# Thermistors.net
KiCad netlist of a schematic drawn in Altium Designer
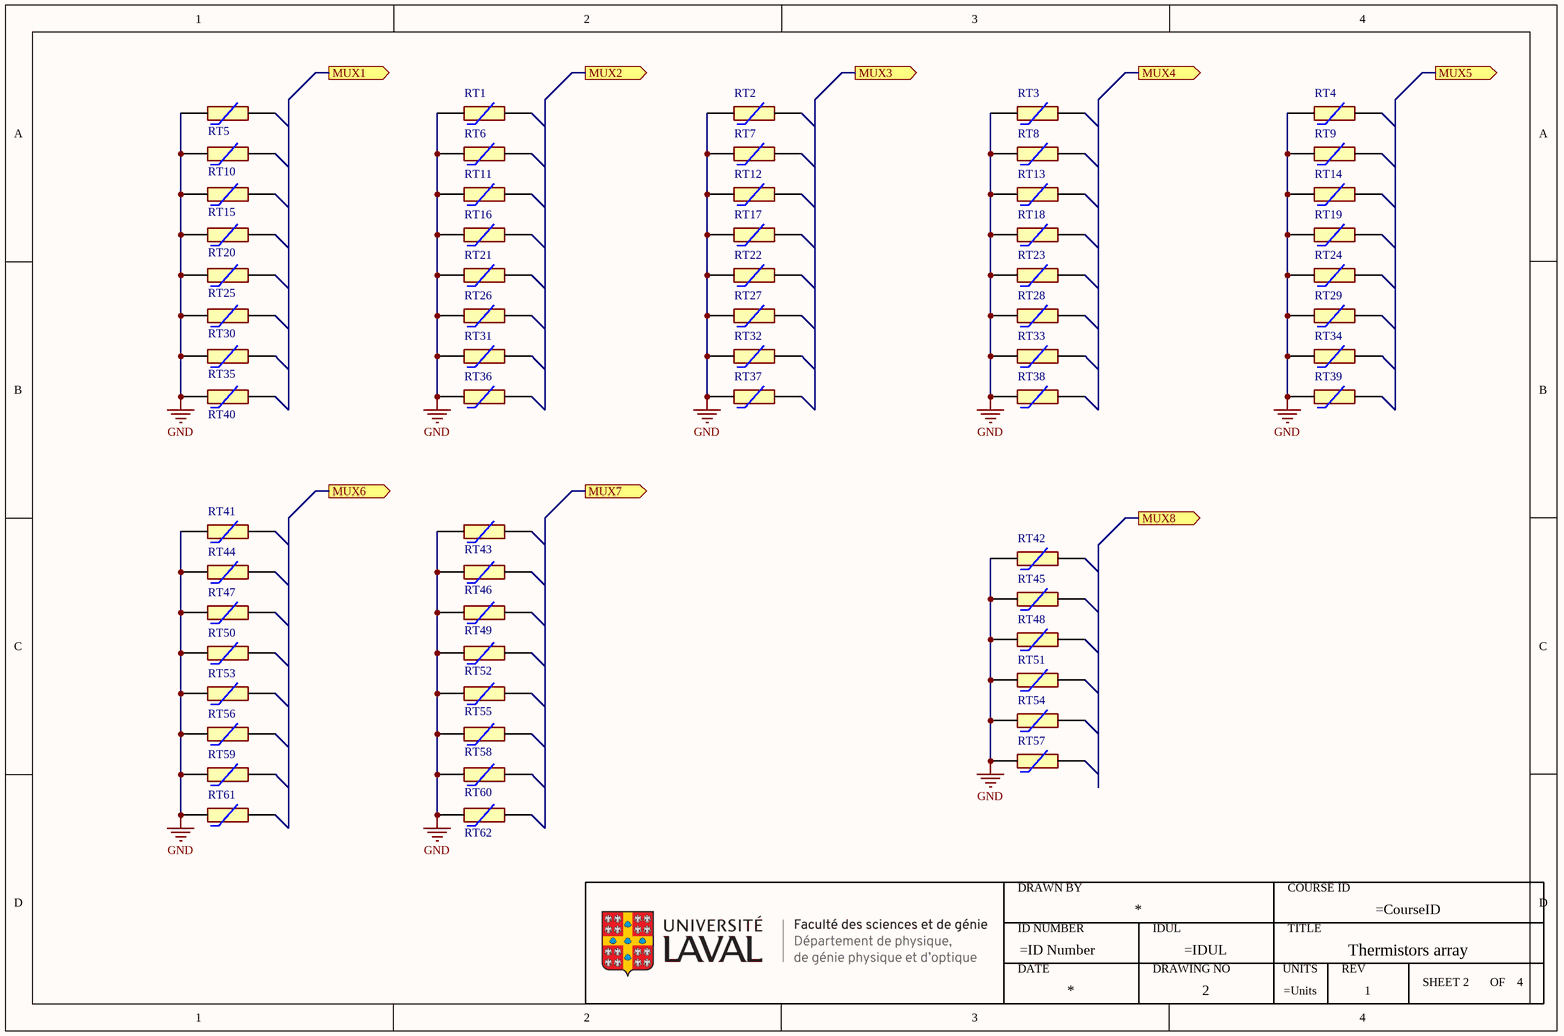
[diagram p0: Thermistors.SchDoc]

(export (version "E")
  (design (tool "Eeschema 10.0.6"))
  (components
    (comp (ref "*2")
      (value "ULaval FSG-DPGPO")
      (libsource (lib "ULaval Title Block") (part "ULaval FSG-DPGPO"))
    )
    (comp (ref "RT1")
      (value "NTCLE350E4103FHB0")
      (footprint "SamacSys:NTCLE350E4103FHB0")
      (description "Thermistor")
      (libsource (lib "*") (part "NTCLE350E4103FHB0"))
    )
    (comp (ref "RT2")
      (value "NTCLE350E4103FHB0")
      (footprint "SamacSys:NTCLE350E4103FHB0")
      (description "Thermistor")
      (libsource (lib "*") (part "NTCLE350E4103FHB0"))
    )
    (comp (ref "RT3")
      (value "NTCLE350E4103FHB0")
      (footprint "SamacSys:NTCLE350E4103FHB0")
      (description "Thermistor")
      (libsource (lib "*") (part "NTCLE350E4103FHB0"))
    )
    (comp (ref "RT4")
      (value "NTCLE350E4103FHB0")
      (footprint "SamacSys:NTCLE350E4103FHB0")
      (description "Thermistor")
      (libsource (lib "*") (part "NTCLE350E4103FHB0"))
    )
    (comp (ref "RT5")
      (value "NTCLE350E4103FHB0")
      (footprint "SamacSys:NTCLE350E4103FHB0")
      (description "Thermistor")
      (libsource (lib "*") (part "NTCLE350E4103FHB0"))
    )
    (comp (ref "RT6")
      (value "NTCLE350E4103FHB0")
      (footprint "SamacSys:NTCLE350E4103FHB0")
      (description "Thermistor")
      (libsource (lib "*") (part "NTCLE350E4103FHB0"))
    )
    (comp (ref "RT7")
      (value "NTCLE350E4103FHB0")
      (footprint "SamacSys:NTCLE350E4103FHB0")
      (description "Thermistor")
      (libsource (lib "*") (part "NTCLE350E4103FHB0"))
    )
    (comp (ref "RT8")
      (value "NTCLE350E4103FHB0")
      (footprint "SamacSys:NTCLE350E4103FHB0")
      (description "Thermistor")
      (libsource (lib "*") (part "NTCLE350E4103FHB0"))
    )
    (comp (ref "RT9")
      (value "NTCLE350E4103FHB0")
      (footprint "SamacSys:NTCLE350E4103FHB0")
      (description "Thermistor")
      (libsource (lib "*") (part "NTCLE350E4103FHB0"))
    )
    (comp (ref "RT10")
      (value "NTCLE350E4103FHB0")
      (footprint "SamacSys:NTCLE350E4103FHB0")
      (description "Thermistor")
      (libsource (lib "*") (part "NTCLE350E4103FHB0"))
    )
    (comp (ref "RT11")
      (value "NTCLE350E4103FHB0")
      (footprint "SamacSys:NTCLE350E4103FHB0")
      (description "Thermistor")
      (libsource (lib "*") (part "NTCLE350E4103FHB0"))
    )
    (comp (ref "RT12")
      (value "NTCLE350E4103FHB0")
      (footprint "SamacSys:NTCLE350E4103FHB0")
      (description "Thermistor")
      (libsource (lib "*") (part "NTCLE350E4103FHB0"))
    )
    (comp (ref "RT13")
      (value "NTCLE350E4103FHB0")
      (footprint "SamacSys:NTCLE350E4103FHB0")
      (description "Thermistor")
      (libsource (lib "*") (part "NTCLE350E4103FHB0"))
    )
    (comp (ref "RT14")
      (value "NTCLE350E4103FHB0")
      (footprint "SamacSys:NTCLE350E4103FHB0")
      (description "Thermistor")
      (libsource (lib "*") (part "NTCLE350E4103FHB0"))
    )
    (comp (ref "RT15")
      (value "NTCLE350E4103FHB0")
      (footprint "SamacSys:NTCLE350E4103FHB0")
      (description "Thermistor")
      (libsource (lib "*") (part "NTCLE350E4103FHB0"))
    )
    (comp (ref "RT16")
      (value "NTCLE350E4103FHB0")
      (footprint "SamacSys:NTCLE350E4103FHB0")
      (description "Thermistor")
      (libsource (lib "*") (part "NTCLE350E4103FHB0"))
    )
    (comp (ref "RT17")
      (value "NTCLE350E4103FHB0")
      (footprint "SamacSys:NTCLE350E4103FHB0")
      (description "Thermistor")
      (libsource (lib "*") (part "NTCLE350E4103FHB0"))
    )
    (comp (ref "RT18")
      (value "NTCLE350E4103FHB0")
      (footprint "SamacSys:NTCLE350E4103FHB0")
      (description "Thermistor")
      (libsource (lib "*") (part "NTCLE350E4103FHB0"))
    )
    (comp (ref "RT19")
      (value "NTCLE350E4103FHB0")
      (footprint "SamacSys:NTCLE350E4103FHB0")
      (description "Thermistor")
      (libsource (lib "*") (part "NTCLE350E4103FHB0"))
    )
    (comp (ref "RT20")
      (value "NTCLE350E4103FHB0")
      (footprint "SamacSys:NTCLE350E4103FHB0")
      (description "Thermistor")
      (libsource (lib "*") (part "NTCLE350E4103FHB0"))
    )
    (comp (ref "RT21")
      (value "NTCLE350E4103FHB0")
      (footprint "SamacSys:NTCLE350E4103FHB0")
      (description "Thermistor")
      (libsource (lib "*") (part "NTCLE350E4103FHB0"))
    )
    (comp (ref "RT22")
      (value "NTCLE350E4103FHB0")
      (footprint "SamacSys:NTCLE350E4103FHB0")
      (description "Thermistor")
      (libsource (lib "*") (part "NTCLE350E4103FHB0"))
    )
    (comp (ref "RT23")
      (value "NTCLE350E4103FHB0")
      (footprint "SamacSys:NTCLE350E4103FHB0")
      (description "Thermistor")
      (libsource (lib "*") (part "NTCLE350E4103FHB0"))
    )
    (comp (ref "RT24")
      (value "NTCLE350E4103FHB0")
      (footprint "SamacSys:NTCLE350E4103FHB0")
      (description "Thermistor")
      (libsource (lib "*") (part "NTCLE350E4103FHB0"))
    )
    (comp (ref "RT25")
      (value "NTCLE350E4103FHB0")
      (footprint "SamacSys:NTCLE350E4103FHB0")
      (description "Thermistor")
      (libsource (lib "*") (part "NTCLE350E4103FHB0"))
    )
    (comp (ref "RT26")
      (value "NTCLE350E4103FHB0")
      (footprint "SamacSys:NTCLE350E4103FHB0")
      (description "Thermistor")
      (libsource (lib "*") (part "NTCLE350E4103FHB0"))
    )
    (comp (ref "RT27")
      (value "NTCLE350E4103FHB0")
      (footprint "SamacSys:NTCLE350E4103FHB0")
      (description "Thermistor")
      (libsource (lib "*") (part "NTCLE350E4103FHB0"))
    )
    (comp (ref "RT28")
      (value "NTCLE350E4103FHB0")
      (footprint "SamacSys:NTCLE350E4103FHB0")
      (description "Thermistor")
      (libsource (lib "*") (part "NTCLE350E4103FHB0"))
    )
    (comp (ref "RT29")
      (value "NTCLE350E4103FHB0")
      (footprint "SamacSys:NTCLE350E4103FHB0")
      (description "Thermistor")
      (libsource (lib "*") (part "NTCLE350E4103FHB0"))
    )
    (comp (ref "RT30")
      (value "NTCLE350E4103FHB0")
      (footprint "SamacSys:NTCLE350E4103FHB0")
      (description "Thermistor")
      (libsource (lib "*") (part "NTCLE350E4103FHB0"))
    )
    (comp (ref "RT31")
      (value "NTCLE350E4103FHB0")
      (footprint "SamacSys:NTCLE350E4103FHB0")
      (description "Thermistor")
      (libsource (lib "*") (part "NTCLE350E4103FHB0"))
    )
    (comp (ref "RT32")
      (value "NTCLE350E4103FHB0")
      (footprint "SamacSys:NTCLE350E4103FHB0")
      (description "Thermistor")
      (libsource (lib "*") (part "NTCLE350E4103FHB0"))
    )
    (comp (ref "RT33")
      (value "NTCLE350E4103FHB0")
      (footprint "SamacSys:NTCLE350E4103FHB0")
      (description "Thermistor")
      (libsource (lib "*") (part "NTCLE350E4103FHB0"))
    )
    (comp (ref "RT34")
      (value "NTCLE350E4103FHB0")
      (footprint "SamacSys:NTCLE350E4103FHB0")
      (description "Thermistor")
      (libsource (lib "*") (part "NTCLE350E4103FHB0"))
    )
    (comp (ref "RT35")
      (value "NTCLE350E4103FHB0")
      (footprint "SamacSys:NTCLE350E4103FHB0")
      (description "Thermistor")
      (libsource (lib "*") (part "NTCLE350E4103FHB0"))
    )
    (comp (ref "RT36")
      (value "NTCLE350E4103FHB0")
      (footprint "SamacSys:NTCLE350E4103FHB0")
      (description "Thermistor")
      (libsource (lib "*") (part "NTCLE350E4103FHB0"))
    )
    (comp (ref "RT37")
      (value "NTCLE350E4103FHB0")
      (footprint "SamacSys:NTCLE350E4103FHB0")
      (description "Thermistor")
      (libsource (lib "*") (part "NTCLE350E4103FHB0"))
    )
    (comp (ref "RT38")
      (value "NTCLE350E4103FHB0")
      (footprint "SamacSys:NTCLE350E4103FHB0")
      (description "Thermistor")
      (libsource (lib "*") (part "NTCLE350E4103FHB0"))
    )
    (comp (ref "RT39")
      (value "NTCLE350E4103FHB0")
      (footprint "SamacSys:NTCLE350E4103FHB0")
      (description "Thermistor")
      (libsource (lib "*") (part "NTCLE350E4103FHB0"))
    )
    (comp (ref "RT40")
      (value "NTCLE350E4103FHB0")
      (footprint "SamacSys:NTCLE350E4103FHB0")
      (description "Thermistor")
      (libsource (lib "*") (part "NTCLE350E4103FHB0"))
    )
    (comp (ref "RT41")
      (value "NTCLE350E4103FHB0")
      (footprint "SamacSys:NTCLE350E4103FHB0")
      (description "Thermistor")
      (libsource (lib "*") (part "NTCLE350E4103FHB0"))
    )
    (comp (ref "RT42")
      (value "NTCLE350E4103FHB0")
      (footprint "SamacSys:NTCLE350E4103FHB0")
      (description "Thermistor")
      (libsource (lib "*") (part "NTCLE350E4103FHB0"))
    )
    (comp (ref "RT43")
      (value "NTCLE350E4103FHB0")
      (footprint "SamacSys:NTCLE350E4103FHB0")
      (description "Thermistor")
      (libsource (lib "*") (part "NTCLE350E4103FHB0"))
    )
    (comp (ref "RT44")
      (value "NTCLE350E4103FHB0")
      (footprint "SamacSys:NTCLE350E4103FHB0")
      (description "Thermistor")
      (libsource (lib "*") (part "NTCLE350E4103FHB0"))
    )
    (comp (ref "RT45")
      (value "NTCLE350E4103FHB0")
      (footprint "SamacSys:NTCLE350E4103FHB0")
      (description "Thermistor")
      (libsource (lib "*") (part "NTCLE350E4103FHB0"))
    )
    (comp (ref "RT46")
      (value "NTCLE350E4103FHB0")
      (footprint "SamacSys:NTCLE350E4103FHB0")
      (description "Thermistor")
      (libsource (lib "*") (part "NTCLE350E4103FHB0"))
    )
    (comp (ref "RT47")
      (value "NTCLE350E4103FHB0")
      (footprint "SamacSys:NTCLE350E4103FHB0")
      (description "Thermistor")
      (libsource (lib "*") (part "NTCLE350E4103FHB0"))
    )
    (comp (ref "RT48")
      (value "NTCLE350E4103FHB0")
      (footprint "SamacSys:NTCLE350E4103FHB0")
      (description "Thermistor")
      (libsource (lib "*") (part "NTCLE350E4103FHB0"))
    )
    (comp (ref "RT49")
      (value "NTCLE350E4103FHB0")
      (footprint "SamacSys:NTCLE350E4103FHB0")
      (description "Thermistor")
      (libsource (lib "*") (part "NTCLE350E4103FHB0"))
    )
    (comp (ref "RT50")
      (value "NTCLE350E4103FHB0")
      (footprint "SamacSys:NTCLE350E4103FHB0")
      (description "Thermistor")
      (libsource (lib "*") (part "NTCLE350E4103FHB0"))
    )
    (comp (ref "RT51")
      (value "NTCLE350E4103FHB0")
      (footprint "SamacSys:NTCLE350E4103FHB0")
      (description "Thermistor")
      (libsource (lib "*") (part "NTCLE350E4103FHB0"))
    )
    (comp (ref "RT52")
      (value "NTCLE350E4103FHB0")
      (footprint "SamacSys:NTCLE350E4103FHB0")
      (description "Thermistor")
      (libsource (lib "*") (part "NTCLE350E4103FHB0"))
    )
    (comp (ref "RT53")
      (value "NTCLE350E4103FHB0")
      (footprint "SamacSys:NTCLE350E4103FHB0")
      (description "Thermistor")
      (libsource (lib "*") (part "NTCLE350E4103FHB0"))
    )
    (comp (ref "RT54")
      (value "NTCLE350E4103FHB0")
      (footprint "SamacSys:NTCLE350E4103FHB0")
      (description "Thermistor")
      (libsource (lib "*") (part "NTCLE350E4103FHB0"))
    )
    (comp (ref "RT55")
      (value "NTCLE350E4103FHB0")
      (footprint "SamacSys:NTCLE350E4103FHB0")
      (description "Thermistor")
      (libsource (lib "*") (part "NTCLE350E4103FHB0"))
    )
    (comp (ref "RT56")
      (value "NTCLE350E4103FHB0")
      (footprint "SamacSys:NTCLE350E4103FHB0")
      (description "Thermistor")
      (libsource (lib "*") (part "NTCLE350E4103FHB0"))
    )
    (comp (ref "RT57")
      (value "NTCLE350E4103FHB0")
      (footprint "SamacSys:NTCLE350E4103FHB0")
      (description "Thermistor")
      (libsource (lib "*") (part "NTCLE350E4103FHB0"))
    )
    (comp (ref "RT58")
      (value "NTCLE350E4103FHB0")
      (footprint "SamacSys:NTCLE350E4103FHB0")
      (description "Thermistor")
      (libsource (lib "*") (part "NTCLE350E4103FHB0"))
    )
    (comp (ref "RT59")
      (value "NTCLE350E4103FHB0")
      (footprint "SamacSys:NTCLE350E4103FHB0")
      (description "Thermistor")
      (libsource (lib "*") (part "NTCLE350E4103FHB0"))
    )
    (comp (ref "RT60")
      (value "NTCLE350E4103FHB0")
      (footprint "SamacSys:NTCLE350E4103FHB0")
      (description "Thermistor")
      (libsource (lib "*") (part "NTCLE350E4103FHB0"))
    )
    (comp (ref "RT61")
      (value "NTCLE350E4103FHB0")
      (footprint "SamacSys:NTCLE350E4103FHB0")
      (description "Thermistor")
      (libsource (lib "*") (part "NTCLE350E4103FHB0"))
    )
    (comp (ref "RT62")
      (value "NTCLE350E4103FHB0")
      (footprint "SamacSys:NTCLE350E4103FHB0")
      (description "Thermistor")
      (libsource (lib "*") (part "NTCLE350E4103FHB0"))
    )
  )
  (nets
    (net (code "9") (name "GND") (class "Default")
      (node (ref "RT1") (pin "1") (pinfunction "1_1") (pintype "passive"))
      (node (ref "RT10") (pin "1") (pinfunction "1_1") (pintype "passive"))
      (node (ref "RT11") (pin "1") (pinfunction "1_1") (pintype "passive"))
      (node (ref "RT12") (pin "1") (pinfunction "1_1") (pintype "passive"))
      (node (ref "RT13") (pin "1") (pinfunction "1_1") (pintype "passive"))
      (node (ref "RT14") (pin "1") (pinfunction "1_1") (pintype "passive"))
      (node (ref "RT15") (pin "1") (pinfunction "1_1") (pintype "passive"))
      (node (ref "RT16") (pin "1") (pinfunction "1_1") (pintype "passive"))
      (node (ref "RT17") (pin "1") (pinfunction "1_1") (pintype "passive"))
      (node (ref "RT18") (pin "1") (pinfunction "1_1") (pintype "passive"))
      (node (ref "RT19") (pin "1") (pinfunction "1_1") (pintype "passive"))
      (node (ref "RT2") (pin "1") (pinfunction "1_1") (pintype "passive"))
      (node (ref "RT20") (pin "1") (pinfunction "1_1") (pintype "passive"))
      (node (ref "RT21") (pin "1") (pinfunction "1_1") (pintype "passive"))
      (node (ref "RT22") (pin "1") (pinfunction "1_1") (pintype "passive"))
      (node (ref "RT23") (pin "1") (pinfunction "1_1") (pintype "passive"))
      (node (ref "RT24") (pin "1") (pinfunction "1_1") (pintype "passive"))
      (node (ref "RT25") (pin "1") (pinfunction "1_1") (pintype "passive"))
      (node (ref "RT26") (pin "1") (pinfunction "1_1") (pintype "passive"))
      (node (ref "RT27") (pin "1") (pinfunction "1_1") (pintype "passive"))
      (node (ref "RT28") (pin "1") (pinfunction "1_1") (pintype "passive"))
      (node (ref "RT29") (pin "1") (pinfunction "1_1") (pintype "passive"))
      (node (ref "RT3") (pin "1") (pinfunction "1_1") (pintype "passive"))
      (node (ref "RT30") (pin "1") (pinfunction "1_1") (pintype "passive"))
      (node (ref "RT31") (pin "1") (pinfunction "1_1") (pintype "passive"))
      (node (ref "RT32") (pin "1") (pinfunction "1_1") (pintype "passive"))
      (node (ref "RT33") (pin "1") (pinfunction "1_1") (pintype "passive"))
      (node (ref "RT34") (pin "1") (pinfunction "1_1") (pintype "passive"))
      (node (ref "RT35") (pin "1") (pinfunction "1_1") (pintype "passive"))
      (node (ref "RT36") (pin "1") (pinfunction "1_1") (pintype "passive"))
      (node (ref "RT37") (pin "1") (pinfunction "1_1") (pintype "passive"))
      (node (ref "RT38") (pin "1") (pinfunction "1_1") (pintype "passive"))
      (node (ref "RT39") (pin "1") (pinfunction "1_1") (pintype "passive"))
      (node (ref "RT4") (pin "1") (pinfunction "1_1") (pintype "passive"))
      (node (ref "RT40") (pin "1") (pinfunction "1_1") (pintype "passive"))
      (node (ref "RT41") (pin "1") (pinfunction "1_1") (pintype "passive"))
      (node (ref "RT42") (pin "1") (pinfunction "1_1") (pintype "passive"))
      (node (ref "RT43") (pin "1") (pinfunction "1_1") (pintype "passive"))
      (node (ref "RT44") (pin "1") (pinfunction "1_1") (pintype "passive"))
      (node (ref "RT45") (pin "1") (pinfunction "1_1") (pintype "passive"))
      (node (ref "RT46") (pin "1") (pinfunction "1_1") (pintype "passive"))
      (node (ref "RT47") (pin "1") (pinfunction "1_1") (pintype "passive"))
      (node (ref "RT48") (pin "1") (pinfunction "1_1") (pintype "passive"))
      (node (ref "RT49") (pin "1") (pinfunction "1_1") (pintype "passive"))
      (node (ref "RT5") (pin "1") (pinfunction "1_1") (pintype "passive"))
      (node (ref "RT50") (pin "1") (pinfunction "1_1") (pintype "passive"))
      (node (ref "RT51") (pin "1") (pinfunction "1_1") (pintype "passive"))
      (node (ref "RT52") (pin "1") (pinfunction "1_1") (pintype "passive"))
      (node (ref "RT53") (pin "1") (pinfunction "1_1") (pintype "passive"))
      (node (ref "RT54") (pin "1") (pinfunction "1_1") (pintype "passive"))
      (node (ref "RT55") (pin "1") (pinfunction "1_1") (pintype "passive"))
      (node (ref "RT56") (pin "1") (pinfunction "1_1") (pintype "passive"))
      (node (ref "RT57") (pin "1") (pinfunction "1_1") (pintype "passive"))
      (node (ref "RT58") (pin "1") (pinfunction "1_1") (pintype "passive"))
      (node (ref "RT59") (pin "1") (pinfunction "1_1") (pintype "passive"))
      (node (ref "RT6") (pin "1") (pinfunction "1_1") (pintype "passive"))
      (node (ref "RT60") (pin "1") (pinfunction "1_1") (pintype "passive"))
      (node (ref "RT61") (pin "1") (pinfunction "1_1") (pintype "passive"))
      (node (ref "RT62") (pin "1") (pinfunction "1_1") (pintype "passive"))
      (node (ref "RT7") (pin "1") (pinfunction "1_1") (pintype "passive"))
      (node (ref "RT8") (pin "1") (pinfunction "1_1") (pintype "passive"))
      (node (ref "RT9") (pin "1") (pinfunction "1_1") (pintype "passive"))
    )
    (net (code "10") (name "unconnected-(RT1-Pad2)") (class "Default")
      (node (ref "RT1") (pin "2") (pinfunction "2_2") (pintype "passive"))
    )
    (net (code "11") (name "unconnected-(RT2-Pad2)") (class "Default")
      (node (ref "RT2") (pin "2") (pinfunction "2_2") (pintype "passive"))
    )
    (net (code "12") (name "unconnected-(RT3-Pad2)") (class "Default")
      (node (ref "RT3") (pin "2") (pinfunction "2_2") (pintype "passive"))
    )
    (net (code "13") (name "unconnected-(RT4-Pad2)") (class "Default")
      (node (ref "RT4") (pin "2") (pinfunction "2_2") (pintype "passive"))
    )
    (net (code "14") (name "unconnected-(RT5-Pad2)") (class "Default")
      (node (ref "RT5") (pin "2") (pinfunction "2_2") (pintype "passive"))
    )
    (net (code "15") (name "unconnected-(RT6-Pad2)") (class "Default")
      (node (ref "RT6") (pin "2") (pinfunction "2_2") (pintype "passive"))
    )
    (net (code "16") (name "unconnected-(RT7-Pad2)") (class "Default")
      (node (ref "RT7") (pin "2") (pinfunction "2_2") (pintype "passive"))
    )
    (net (code "17") (name "unconnected-(RT8-Pad2)") (class "Default")
      (node (ref "RT8") (pin "2") (pinfunction "2_2") (pintype "passive"))
    )
    (net (code "18") (name "unconnected-(RT9-Pad2)") (class "Default")
      (node (ref "RT9") (pin "2") (pinfunction "2_2") (pintype "passive"))
    )
    (net (code "19") (name "unconnected-(RT10-Pad2)") (class "Default")
      (node (ref "RT10") (pin "2") (pinfunction "2_2") (pintype "passive"))
    )
    (net (code "20") (name "unconnected-(RT11-Pad2)") (class "Default")
      (node (ref "RT11") (pin "2") (pinfunction "2_2") (pintype "passive"))
    )
    (net (code "21") (name "unconnected-(RT12-Pad2)") (class "Default")
      (node (ref "RT12") (pin "2") (pinfunction "2_2") (pintype "passive"))
    )
    (net (code "22") (name "unconnected-(RT13-Pad2)") (class "Default")
      (node (ref "RT13") (pin "2") (pinfunction "2_2") (pintype "passive"))
    )
    (net (code "23") (name "unconnected-(RT14-Pad2)") (class "Default")
      (node (ref "RT14") (pin "2") (pinfunction "2_2") (pintype "passive"))
    )
    (net (code "24") (name "unconnected-(RT15-Pad2)") (class "Default")
      (node (ref "RT15") (pin "2") (pinfunction "2_2") (pintype "passive"))
    )
    (net (code "25") (name "unconnected-(RT16-Pad2)") (class "Default")
      (node (ref "RT16") (pin "2") (pinfunction "2_2") (pintype "passive"))
    )
    (net (code "26") (name "unconnected-(RT17-Pad2)") (class "Default")
      (node (ref "RT17") (pin "2") (pinfunction "2_2") (pintype "passive"))
    )
    (net (code "27") (name "unconnected-(RT18-Pad2)") (class "Default")
      (node (ref "RT18") (pin "2") (pinfunction "2_2") (pintype "passive"))
    )
    (net (code "28") (name "unconnected-(RT19-Pad2)") (class "Default")
      (node (ref "RT19") (pin "2") (pinfunction "2_2") (pintype "passive"))
    )
    (net (code "29") (name "unconnected-(RT20-Pad2)") (class "Default")
      (node (ref "RT20") (pin "2") (pinfunction "2_2") (pintype "passive"))
    )
    (net (code "30") (name "unconnected-(RT21-Pad2)") (class "Default")
      (node (ref "RT21") (pin "2") (pinfunction "2_2") (pintype "passive"))
    )
    (net (code "31") (name "unconnected-(RT22-Pad2)") (class "Default")
      (node (ref "RT22") (pin "2") (pinfunction "2_2") (pintype "passive"))
    )
    (net (code "32") (name "unconnected-(RT23-Pad2)") (class "Default")
      (node (ref "RT23") (pin "2") (pinfunction "2_2") (pintype "passive"))
    )
    (net (code "33") (name "unconnected-(RT24-Pad2)") (class "Default")
      (node (ref "RT24") (pin "2") (pinfunction "2_2") (pintype "passive"))
    )
    (net (code "34") (name "unconnected-(RT25-Pad2)") (class "Default")
      (node (ref "RT25") (pin "2") (pinfunction "2_2") (pintype "passive"))
    )
    (net (code "35") (name "unconnected-(RT26-Pad2)") (class "Default")
      (node (ref "RT26") (pin "2") (pinfunction "2_2") (pintype "passive"))
    )
    (net (code "36") (name "unconnected-(RT27-Pad2)") (class "Default")
      (node (ref "RT27") (pin "2") (pinfunction "2_2") (pintype "passive"))
    )
    (net (code "37") (name "unconnected-(RT28-Pad2)") (class "Default")
      (node (ref "RT28") (pin "2") (pinfunction "2_2") (pintype "passive"))
    )
    (net (code "38") (name "unconnected-(RT29-Pad2)") (class "Default")
      (node (ref "RT29") (pin "2") (pinfunction "2_2") (pintype "passive"))
    )
    (net (code "39") (name "unconnected-(RT30-Pad2)") (class "Default")
      (node (ref "RT30") (pin "2") (pinfunction "2_2") (pintype "passive"))
    )
    (net (code "40") (name "unconnected-(RT31-Pad2)") (class "Default")
      (node (ref "RT31") (pin "2") (pinfunction "2_2") (pintype "passive"))
    )
    (net (code "41") (name "unconnected-(RT32-Pad2)") (class "Default")
      (node (ref "RT32") (pin "2") (pinfunction "2_2") (pintype "passive"))
    )
    (net (code "42") (name "unconnected-(RT33-Pad2)") (class "Default")
      (node (ref "RT33") (pin "2") (pinfunction "2_2") (pintype "passive"))
    )
    (net (code "43") (name "unconnected-(RT34-Pad2)") (class "Default")
      (node (ref "RT34") (pin "2") (pinfunction "2_2") (pintype "passive"))
    )
    (net (code "44") (name "unconnected-(RT35-Pad2)") (class "Default")
      (node (ref "RT35") (pin "2") (pinfunction "2_2") (pintype "passive"))
    )
    (net (code "45") (name "unconnected-(RT36-Pad2)") (class "Default")
      (node (ref "RT36") (pin "2") (pinfunction "2_2") (pintype "passive"))
    )
    (net (code "46") (name "unconnected-(RT37-Pad2)") (class "Default")
      (node (ref "RT37") (pin "2") (pinfunction "2_2") (pintype "passive"))
    )
    (net (code "47") (name "unconnected-(RT38-Pad2)") (class "Default")
      (node (ref "RT38") (pin "2") (pinfunction "2_2") (pintype "passive"))
    )
    (net (code "48") (name "unconnected-(RT39-Pad2)") (class "Default")
      (node (ref "RT39") (pin "2") (pinfunction "2_2") (pintype "passive"))
    )
    (net (code "49") (name "unconnected-(RT40-Pad2)") (class "Default")
      (node (ref "RT40") (pin "2") (pinfunction "2_2") (pintype "passive"))
    )
    (net (code "50") (name "unconnected-(RT41-Pad2)") (class "Default")
      (node (ref "RT41") (pin "2") (pinfunction "2_2") (pintype "passive"))
    )
    (net (code "51") (name "unconnected-(RT42-Pad2)") (class "Default")
      (node (ref "RT42") (pin "2") (pinfunction "2_2") (pintype "passive"))
    )
    (net (code "52") (name "unconnected-(RT43-Pad2)") (class "Default")
      (node (ref "RT43") (pin "2") (pinfunction "2_2") (pintype "passive"))
    )
    (net (code "53") (name "unconnected-(RT44-Pad2)") (class "Default")
      (node (ref "RT44") (pin "2") (pinfunction "2_2") (pintype "passive"))
    )
    (net (code "54") (name "unconnected-(RT45-Pad2)") (class "Default")
      (node (ref "RT45") (pin "2") (pinfunction "2_2") (pintype "passive"))
    )
    (net (code "55") (name "unconnected-(RT46-Pad2)") (class "Default")
      (node (ref "RT46") (pin "2") (pinfunction "2_2") (pintype "passive"))
    )
    (net (code "56") (name "unconnected-(RT47-Pad2)") (class "Default")
      (node (ref "RT47") (pin "2") (pinfunction "2_2") (pintype "passive"))
    )
    (net (code "57") (name "unconnected-(RT48-Pad2)") (class "Default")
      (node (ref "RT48") (pin "2") (pinfunction "2_2") (pintype "passive"))
    )
    (net (code "58") (name "unconnected-(RT49-Pad2)") (class "Default")
      (node (ref "RT49") (pin "2") (pinfunction "2_2") (pintype "passive"))
    )
    (net (code "59") (name "unconnected-(RT50-Pad2)") (class "Default")
      (node (ref "RT50") (pin "2") (pinfunction "2_2") (pintype "passive"))
    )
    (net (code "60") (name "unconnected-(RT51-Pad2)") (class "Default")
      (node (ref "RT51") (pin "2") (pinfunction "2_2") (pintype "passive"))
    )
    (net (code "61") (name "unconnected-(RT52-Pad2)") (class "Default")
      (node (ref "RT52") (pin "2") (pinfunction "2_2") (pintype "passive"))
    )
    (net (code "62") (name "unconnected-(RT53-Pad2)") (class "Default")
      (node (ref "RT53") (pin "2") (pinfunction "2_2") (pintype "passive"))
    )
    (net (code "63") (name "unconnected-(RT54-Pad2)") (class "Default")
      (node (ref "RT54") (pin "2") (pinfunction "2_2") (pintype "passive"))
    )
    (net (code "64") (name "unconnected-(RT55-Pad2)") (class "Default")
      (node (ref "RT55") (pin "2") (pinfunction "2_2") (pintype "passive"))
    )
    (net (code "65") (name "unconnected-(RT56-Pad2)") (class "Default")
      (node (ref "RT56") (pin "2") (pinfunction "2_2") (pintype "passive"))
    )
    (net (code "66") (name "unconnected-(RT57-Pad2)") (class "Default")
      (node (ref "RT57") (pin "2") (pinfunction "2_2") (pintype "passive"))
    )
    (net (code "67") (name "unconnected-(RT58-Pad2)") (class "Default")
      (node (ref "RT58") (pin "2") (pinfunction "2_2") (pintype "passive"))
    )
    (net (code "68") (name "unconnected-(RT59-Pad2)") (class "Default")
      (node (ref "RT59") (pin "2") (pinfunction "2_2") (pintype "passive"))
    )
    (net (code "69") (name "unconnected-(RT60-Pad2)") (class "Default")
      (node (ref "RT60") (pin "2") (pinfunction "2_2") (pintype "passive"))
    )
    (net (code "70") (name "unconnected-(RT61-Pad2)") (class "Default")
      (node (ref "RT61") (pin "2") (pinfunction "2_2") (pintype "passive"))
    )
    (net (code "71") (name "unconnected-(RT62-Pad2)") (class "Default")
      (node (ref "RT62") (pin "2") (pinfunction "2_2") (pintype "passive"))
    )
  )
)
